# Lumiboard-SMD-DX-v003-stew.net
KiCad netlist of a schematic drawn in EAGLE
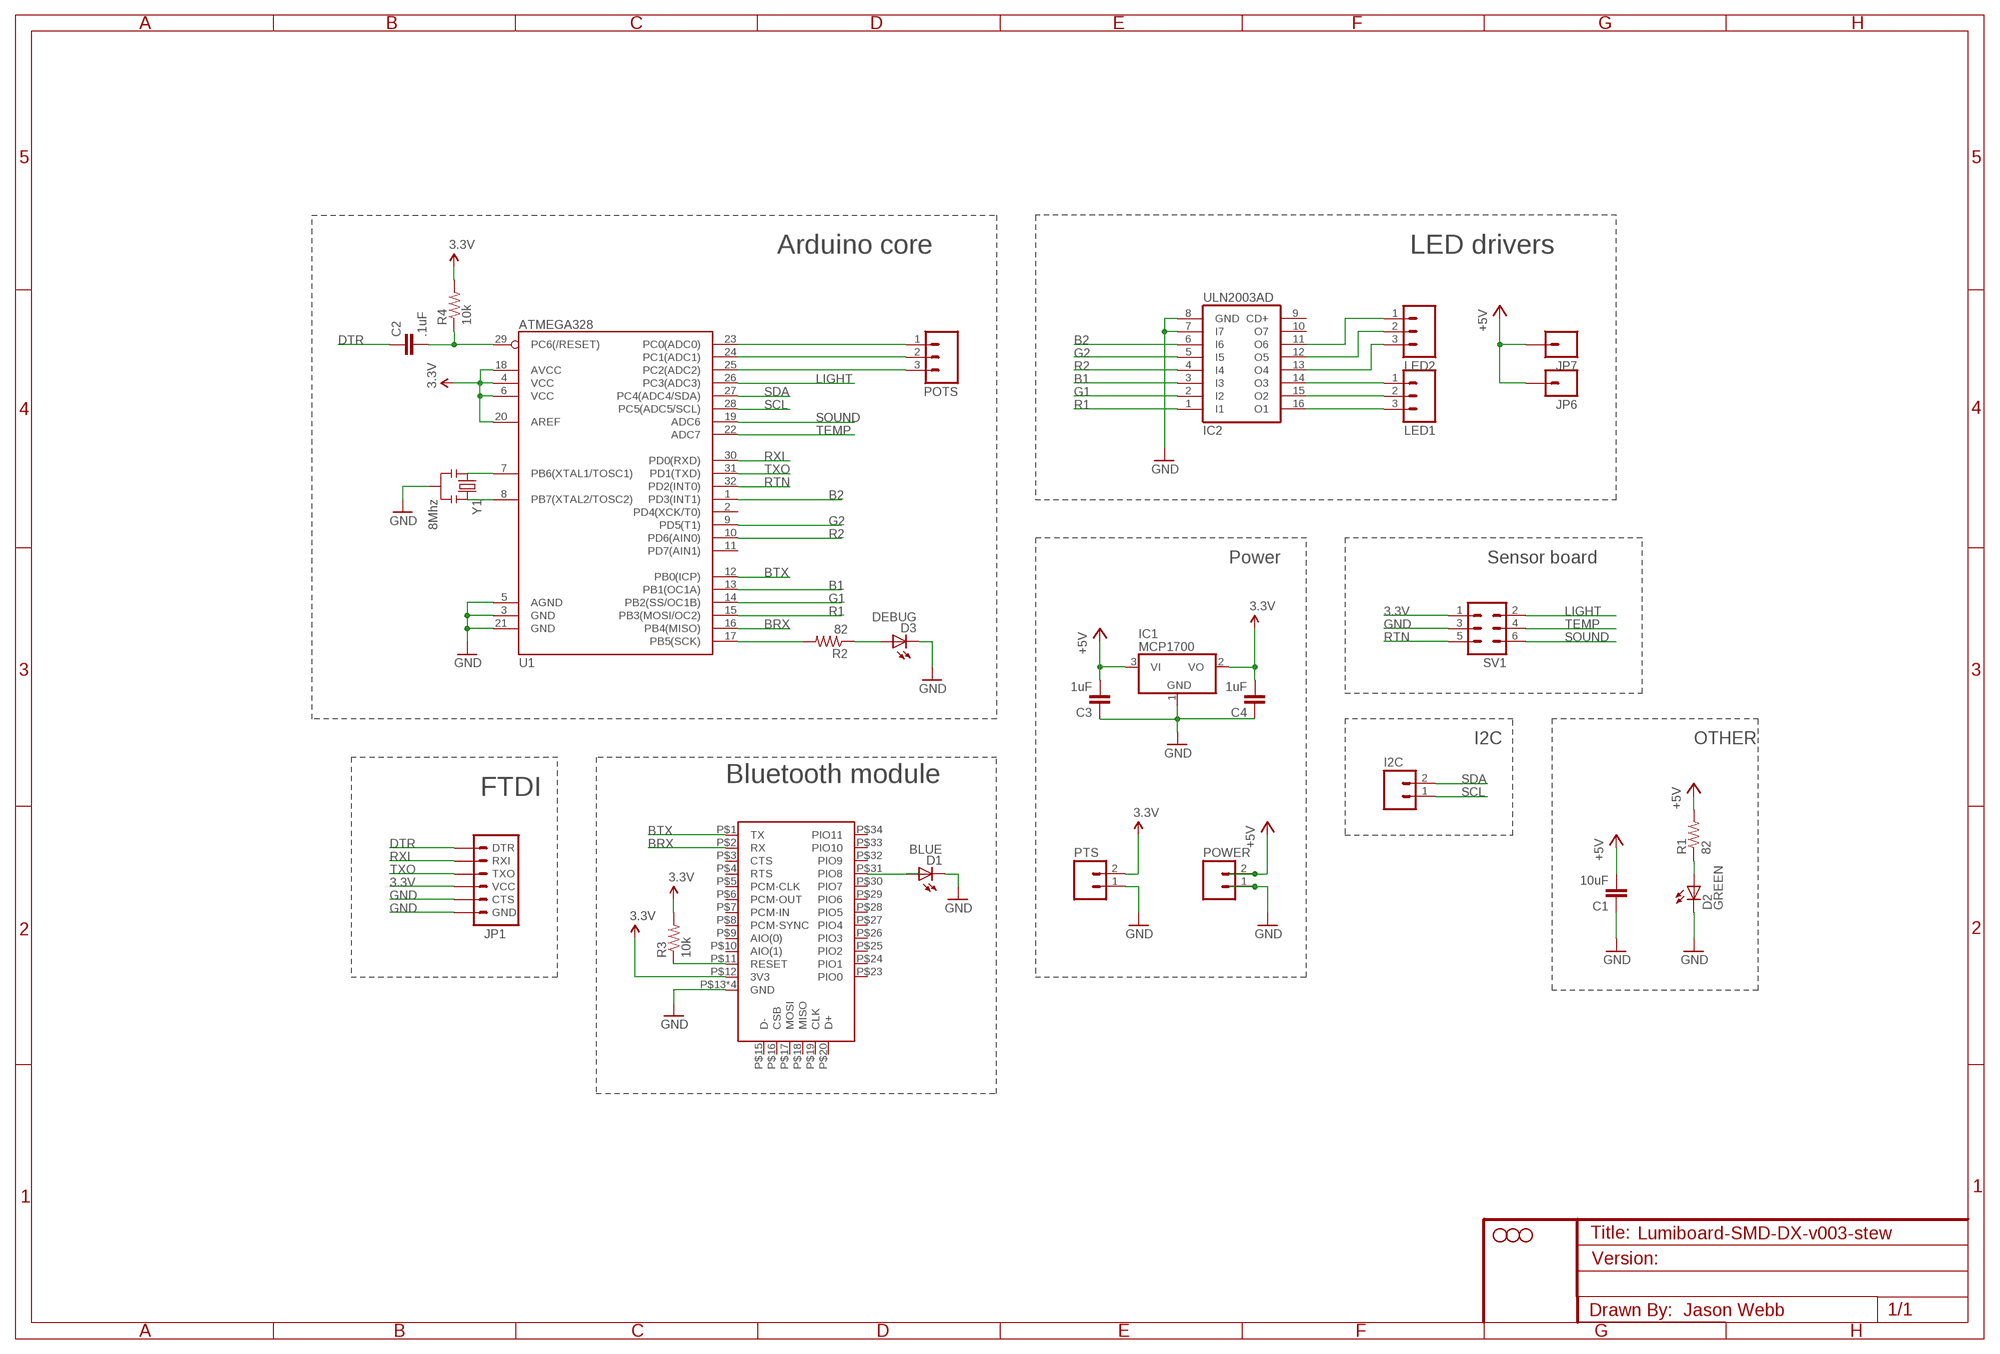
[diagram p0: schematic, sheet 1]

(export (version "E")
  (design (tool "Eeschema 10.0.6"))
  (components
    (comp (ref "C1")
      (value "10uF")
      (footprint "eagle-import:0805")
      (libsource (lib "eagle-import") (part "CAP0805"))
    )
    (comp (ref "C2")
      (value ".1uF")
      (footprint "eagle-import:0805")
      (libsource (lib "eagle-import") (part "CAP0805"))
    )
    (comp (ref "C3")
      (value "1uF")
      (footprint "eagle-import:0805")
      (libsource (lib "eagle-import") (part "CAP0805"))
    )
    (comp (ref "C4")
      (value "1uF")
      (footprint "eagle-import:0805")
      (libsource (lib "eagle-import") (part "CAP0805"))
    )
    (comp (ref "D1")
      (value "BLUE")
      (footprint "eagle-import:CHIPLED_0805")
      (libsource (lib "eagle-import") (part "LEDCHIPLED_0805"))
    )
    (comp (ref "D2")
      (value "GREEN")
      (footprint "eagle-import:CHIPLED_0805")
      (libsource (lib "eagle-import") (part "LEDCHIPLED_0805"))
    )
    (comp (ref "D3")
      (value "DEBUG")
      (footprint "eagle-import:CHIPLED_0805")
      (libsource (lib "eagle-import") (part "LEDCHIPLED_0805"))
    )
    (comp (ref "I2C")
      (value "M02PTH")
      (footprint "eagle-import:1X02")
      (libsource (lib "eagle-import") (part "M02PTH"))
    )
    (comp (ref "IC1")
      (value "MCP1700")
      (footprint "eagle-import:SOT23")
      (libsource (lib "eagle-import") (part "MCP1703CB"))
    )
    (comp (ref "IC2")
      (value "ULN2003AD")
      (footprint "eagle-import:SO16")
      (libsource (lib "eagle-import") (part "ULN2003AD"))
    )
    (comp (ref "JP1")
      (value "ARDUINO_SERIAL_PROGRAMLOCK")
      (footprint "eagle-import:1X06_LOCK")
      (libsource (lib "eagle-import") (part "ARDUINO_SERIAL_PROGRAMLOCK"))
    )
    (comp (ref "JP2")
      (value "STAND-OFFTIGHT")
      (footprint "eagle-import:STAND-OFF-TIGHT")
      (libsource (lib "eagle-import") (part "STAND-OFFTIGHT"))
    )
    (comp (ref "JP4")
      (value "STAND-OFFTIGHT")
      (footprint "eagle-import:STAND-OFF-TIGHT")
      (libsource (lib "eagle-import") (part "STAND-OFFTIGHT"))
    )
    (comp (ref "JP5")
      (value "STAND-OFFTIGHT")
      (footprint "eagle-import:STAND-OFF-TIGHT")
      (libsource (lib "eagle-import") (part "STAND-OFFTIGHT"))
    )
    (comp (ref "JP6")
      (value "M01PTH")
      (footprint "eagle-import:1X01")
      (libsource (lib "eagle-import") (part "M01PTH"))
    )
    (comp (ref "JP7")
      (value "M01PTH")
      (footprint "eagle-import:1X01")
      (libsource (lib "eagle-import") (part "M01PTH"))
    )
    (comp (ref "LED1")
      (value "M03PTH")
      (footprint "eagle-import:1X03")
      (libsource (lib "eagle-import") (part "M03PTH"))
    )
    (comp (ref "LED2")
      (value "M03PTH")
      (footprint "eagle-import:1X03")
      (libsource (lib "eagle-import") (part "M03PTH"))
    )
    (comp (ref "POTS")
      (value "M03PTH")
      (footprint "eagle-import:1X03")
      (libsource (lib "eagle-import") (part "M03PTH"))
    )
    (comp (ref "POWER")
      (value "M02PTH")
      (footprint "eagle-import:1X02")
      (libsource (lib "eagle-import") (part "M02PTH"))
    )
    (comp (ref "PTS")
      (value "M02PTH")
      (footprint "eagle-import:1X02")
      (libsource (lib "eagle-import") (part "M02PTH"))
    )
    (comp (ref "R1")
      (value "82")
      (footprint "eagle-import:R0805")
      (libsource (lib "eagle-import") (part "R-US_R0805"))
    )
    (comp (ref "R2")
      (value "82")
      (footprint "eagle-import:R0805")
      (libsource (lib "eagle-import") (part "R-US_R0805"))
    )
    (comp (ref "R3")
      (value "10k")
      (footprint "eagle-import:R0805")
      (libsource (lib "eagle-import") (part "R-US_R0805"))
    )
    (comp (ref "R4")
      (value "10k")
      (footprint "eagle-import:R0805")
      (libsource (lib "eagle-import") (part "R-US_R0805"))
    )
    (comp (ref "SV1")
      (value "ML6")
      (footprint "eagle-import:ML6")
      (libsource (lib "eagle-import") (part "ML6"))
    )
    (comp (ref "U1")
      (value "ATMEGA328")
      (footprint "eagle-import:TQFP32-08")
      (libsource (lib "eagle-import") (part "ATMEGA168"))
    )
    (comp (ref "U2")
      (value "DX_BT_MODULE")
      (footprint "eagle-import:DXBLUETOOTHMODULE")
      (libsource (lib "eagle-import") (part "DX_BT_MODULE"))
    )
    (comp (ref "Y1")
      (value "8Mhz")
      (footprint "eagle-import:RESONATOR-SMD")
      (libsource (lib "eagle-import") (part "RESONATORSMD"))
    )
  )
  (nets
    (net (code "1") (name "+5V") (class "Default")
      (node (ref "C1") (pin "2") (pinfunction "2_2") (pintype "passive"))
      (node (ref "C3") (pin "2") (pinfunction "2_2") (pintype "passive"))
      (node (ref "IC1") (pin "3") (pinfunction "VI_3") (pintype "input"))
      (node (ref "JP6") (pin "1") (pinfunction "1_1") (pintype "passive"))
      (node (ref "JP7") (pin "1") (pinfunction "1_1") (pintype "passive"))
      (node (ref "POWER") (pin "2") (pinfunction "2_2") (pintype "passive"))
      (node (ref "R1") (pin "2") (pinfunction "2_2") (pintype "passive"))
    )
    (net (code "2") (name "/B1") (class "Default")
      (node (ref "IC2") (pin "3") (pinfunction "I3_3") (pintype "input"))
      (node (ref "U1") (pin "13") (pinfunction "PB1(OC1A)_13") (pintype "bidirectional"))
    )
    (net (code "3") (name "/B2") (class "Default")
      (node (ref "IC2") (pin "6") (pinfunction "I6_6") (pintype "input"))
      (node (ref "U1") (pin "1") (pinfunction "PD3(INT1)_1") (pintype "bidirectional"))
    )
    (net (code "4") (name "/BRX") (class "Default")
      (node (ref "U1") (pin "16") (pinfunction "PB4(MISO)_16") (pintype "bidirectional"))
      (node (ref "U2") (pin "P$2") (pinfunction "RX_P$2") (pintype "input"))
    )
    (net (code "5") (name "/BTX") (class "Default")
      (node (ref "U1") (pin "12") (pinfunction "PB0(ICP)_12") (pintype "bidirectional"))
      (node (ref "U2") (pin "P$1") (pinfunction "TX_P$1") (pintype "output"))
    )
    (net (code "6") (name "/DTR") (class "Default")
      (node (ref "C2") (pin "1") (pinfunction "1_1") (pintype "passive"))
      (node (ref "JP1") (pin "1") (pinfunction "DTR_1") (pintype "passive"))
    )
    (net (code "7") (name "/G1") (class "Default")
      (node (ref "IC2") (pin "2") (pinfunction "I2_2") (pintype "input"))
      (node (ref "U1") (pin "14") (pinfunction "PB2(SS/OC1B)_14") (pintype "bidirectional"))
    )
    (net (code "8") (name "/G2") (class "Default")
      (node (ref "IC2") (pin "5") (pinfunction "I5_5") (pintype "input"))
      (node (ref "U1") (pin "9") (pinfunction "PD5(T1)_9") (pintype "bidirectional"))
    )
    (net (code "9") (name "/LIGHT") (class "Default")
      (node (ref "SV1") (pin "2") (pinfunction "2_2") (pintype "passive"))
      (node (ref "U1") (pin "26") (pinfunction "PC3(ADC3)_26") (pintype "bidirectional"))
    )
    (net (code "10") (name "/R1") (class "Default")
      (node (ref "IC2") (pin "1") (pinfunction "I1_1") (pintype "input"))
      (node (ref "U1") (pin "15") (pinfunction "PB3(MOSI/OC2)_15") (pintype "bidirectional"))
    )
    (net (code "11") (name "/R2") (class "Default")
      (node (ref "IC2") (pin "4") (pinfunction "I4_4") (pintype "input"))
      (node (ref "U1") (pin "10") (pinfunction "PD6(AIN0)_10") (pintype "bidirectional"))
    )
    (net (code "12") (name "/RTN") (class "Default")
      (node (ref "SV1") (pin "5") (pinfunction "5_5") (pintype "passive"))
      (node (ref "U1") (pin "32") (pinfunction "PD2(INT0)_32") (pintype "bidirectional"))
    )
    (net (code "13") (name "/RXI") (class "Default")
      (node (ref "JP1") (pin "2") (pinfunction "RXI_2") (pintype "passive"))
      (node (ref "U1") (pin "30") (pinfunction "PD0(RXD)_30") (pintype "bidirectional"))
    )
    (net (code "14") (name "/SCL") (class "Default")
      (node (ref "I2C") (pin "1") (pinfunction "1_1") (pintype "passive"))
      (node (ref "U1") (pin "28") (pinfunction "PC5(ADC5/SCL)_28") (pintype "bidirectional"))
    )
    (net (code "15") (name "/SDA") (class "Default")
      (node (ref "I2C") (pin "2") (pinfunction "2_2") (pintype "passive"))
      (node (ref "U1") (pin "27") (pinfunction "PC4(ADC4/SDA)_27") (pintype "bidirectional"))
    )
    (net (code "16") (name "/SOUND") (class "Default")
      (node (ref "SV1") (pin "6") (pinfunction "6_6") (pintype "passive"))
      (node (ref "U1") (pin "19") (pinfunction "ADC6_19") (pintype "bidirectional"))
    )
    (net (code "17") (name "/TEMP") (class "Default")
      (node (ref "SV1") (pin "4") (pinfunction "4_4") (pintype "passive"))
      (node (ref "U1") (pin "22") (pinfunction "ADC7_22") (pintype "bidirectional"))
    )
    (net (code "18") (name "/TXO") (class "Default")
      (node (ref "JP1") (pin "3") (pinfunction "TXO_3") (pintype "passive"))
      (node (ref "U1") (pin "31") (pinfunction "PD1(TXD)_31") (pintype "bidirectional"))
    )
    (net (code "19") (name "3.3V") (class "Default")
      (node (ref "C4") (pin "2") (pinfunction "2_2") (pintype "passive"))
      (node (ref "IC1") (pin "2") (pinfunction "VO_2") (pintype "passive"))
      (node (ref "JP1") (pin "4") (pinfunction "VCC_4") (pintype "passive"))
      (node (ref "PTS") (pin "2") (pinfunction "2_2") (pintype "passive"))
      (node (ref "R3") (pin "2") (pinfunction "2_2") (pintype "passive"))
      (node (ref "R4") (pin "2") (pinfunction "2_2") (pintype "passive"))
      (node (ref "SV1") (pin "1") (pinfunction "1_1") (pintype "passive"))
      (node (ref "U1") (pin "18") (pinfunction "AVCC_18") (pintype "bidirectional"))
      (node (ref "U1") (pin "20") (pinfunction "AREF_20") (pintype "bidirectional"))
      (node (ref "U1") (pin "4") (pinfunction "VCC_4") (pintype "bidirectional"))
      (node (ref "U1") (pin "6") (pinfunction "VCC_6") (pintype "bidirectional"))
      (node (ref "U2") (pin "P$12") (pinfunction "3V3_P$12") (pintype "power_in"))
    )
    (net (code "20") (name "GND") (class "Default")
      (node (ref "C1") (pin "1") (pinfunction "1_1") (pintype "passive"))
      (node (ref "C3") (pin "1") (pinfunction "1_1") (pintype "passive"))
      (node (ref "C4") (pin "1") (pinfunction "1_1") (pintype "passive"))
      (node (ref "D1") (pin "C") (pinfunction "C_C") (pintype "passive"))
      (node (ref "D2") (pin "C") (pinfunction "C_C") (pintype "passive"))
      (node (ref "D3") (pin "C") (pinfunction "C_C") (pintype "passive"))
      (node (ref "IC1") (pin "1") (pinfunction "GND_1") (pintype "passive"))
      (node (ref "IC2") (pin "7") (pinfunction "I7_7") (pintype "input"))
      (node (ref "IC2") (pin "8") (pinfunction "GND_8") (pintype "power_in"))
      (node (ref "JP1") (pin "5") (pinfunction "CTS_5") (pintype "passive"))
      (node (ref "JP1") (pin "6") (pinfunction "GND_6") (pintype "passive"))
      (node (ref "POWER") (pin "1") (pinfunction "1_1") (pintype "passive"))
      (node (ref "PTS") (pin "1") (pinfunction "1_1") (pintype "passive"))
      (node (ref "SV1") (pin "3") (pinfunction "3_3") (pintype "passive"))
      (node (ref "U1") (pin "21") (pinfunction "GND_21") (pintype "bidirectional"))
      (node (ref "U1") (pin "3") (pinfunction "GND_3") (pintype "bidirectional"))
      (node (ref "U1") (pin "5") (pinfunction "AGND_5") (pintype "bidirectional"))
      (node (ref "U2") (pin "P$13") (pinfunction "GND_P$13") (pintype "power_in"))
      (node (ref "U2") (pin "P$14") (pinfunction "GND_P$14") (pintype "power_in"))
      (node (ref "U2") (pin "P$21") (pinfunction "GND_P$21") (pintype "power_in"))
      (node (ref "U2") (pin "P$22") (pinfunction "GND_P$22") (pintype "power_in"))
      (node (ref "Y1") (pin "2") (pinfunction "2_2") (pintype "passive"))
    )
    (net (code "21") (name "Net-(D2-PadA)") (class "Default")
      (node (ref "D2") (pin "A") (pinfunction "A_A") (pintype "passive"))
      (node (ref "R1") (pin "1") (pinfunction "1_1") (pintype "passive"))
    )
    (net (code "22") (name "Net-(D3-PadA)") (class "Default")
      (node (ref "D3") (pin "A") (pinfunction "A_A") (pintype "passive"))
      (node (ref "R2") (pin "1") (pinfunction "1_1") (pintype "passive"))
    )
    (net (code "23") (name "Net-(IC2-O1)") (class "Default")
      (node (ref "IC2") (pin "16") (pinfunction "O1_16") (pintype "open_collector"))
      (node (ref "LED1") (pin "3") (pinfunction "3_3") (pintype "passive"))
    )
    (net (code "24") (name "Net-(IC2-O2)") (class "Default")
      (node (ref "IC2") (pin "15") (pinfunction "O2_15") (pintype "open_collector"))
      (node (ref "LED1") (pin "2") (pinfunction "2_2") (pintype "passive"))
    )
    (net (code "25") (name "Net-(IC2-O3)") (class "Default")
      (node (ref "IC2") (pin "14") (pinfunction "O3_14") (pintype "open_collector"))
      (node (ref "LED1") (pin "1") (pinfunction "1_1") (pintype "passive"))
    )
    (net (code "26") (name "Net-(IC2-O4)") (class "Default")
      (node (ref "IC2") (pin "13") (pinfunction "O4_13") (pintype "open_collector"))
      (node (ref "LED2") (pin "3") (pinfunction "3_3") (pintype "passive"))
    )
    (net (code "27") (name "Net-(IC2-O5)") (class "Default")
      (node (ref "IC2") (pin "12") (pinfunction "O5_12") (pintype "open_collector"))
      (node (ref "LED2") (pin "2") (pinfunction "2_2") (pintype "passive"))
    )
    (net (code "28") (name "Net-(IC2-O6)") (class "Default")
      (node (ref "IC2") (pin "11") (pinfunction "O6_11") (pintype "open_collector"))
      (node (ref "LED2") (pin "1") (pinfunction "1_1") (pintype "passive"))
    )
    (net (code "29") (name "Net-(U1-PB5(SCK))") (class "Default")
      (node (ref "R2") (pin "2") (pinfunction "2_2") (pintype "passive"))
      (node (ref "U1") (pin "17") (pinfunction "PB5(SCK)_17") (pintype "bidirectional"))
    )
    (net (code "30") (name "Net-(U1-PB6(XTAL1{slash}TOSC1))") (class "Default")
      (node (ref "U1") (pin "7") (pinfunction "PB6(XTAL1/TOSC1)_7") (pintype "bidirectional"))
      (node (ref "Y1") (pin "1") (pinfunction "1_1") (pintype "passive"))
    )
    (net (code "31") (name "Net-(U1-PB7(XTAL2{slash}TOSC2))") (class "Default")
      (node (ref "U1") (pin "8") (pinfunction "PB7(XTAL2/TOSC2)_8") (pintype "bidirectional"))
      (node (ref "Y1") (pin "3") (pinfunction "3_3") (pintype "passive"))
    )
    (net (code "32") (name "Net-(U1-PC0(ADC0))") (class "Default")
      (node (ref "POTS") (pin "1") (pinfunction "1_1") (pintype "passive"))
      (node (ref "U1") (pin "23") (pinfunction "PC0(ADC0)_23") (pintype "bidirectional"))
    )
    (net (code "33") (name "Net-(U1-PC1(ADC1))") (class "Default")
      (node (ref "POTS") (pin "2") (pinfunction "2_2") (pintype "passive"))
      (node (ref "U1") (pin "24") (pinfunction "PC1(ADC1)_24") (pintype "bidirectional"))
    )
    (net (code "34") (name "Net-(U1-PC2(ADC2))") (class "Default")
      (node (ref "POTS") (pin "3") (pinfunction "3_3") (pintype "passive"))
      (node (ref "U1") (pin "25") (pinfunction "PC2(ADC2)_25") (pintype "bidirectional"))
    )
    (net (code "35") (name "Net-(U1-PC6({slash}RESET))") (class "Default")
      (node (ref "C2") (pin "2") (pinfunction "2_2") (pintype "passive"))
      (node (ref "R4") (pin "1") (pinfunction "1_1") (pintype "passive"))
      (node (ref "U1") (pin "29") (pinfunction "PC6(/RESET)_29") (pintype "bidirectional"))
    )
    (net (code "36") (name "Net-(U2-PIO8)") (class "Default")
      (node (ref "D1") (pin "A") (pinfunction "A_A") (pintype "passive"))
      (node (ref "U2") (pin "P$31") (pinfunction "PIO8_P$31") (pintype "bidirectional"))
    )
    (net (code "37") (name "Net-(U2-RESET)") (class "Default")
      (node (ref "R3") (pin "1") (pinfunction "1_1") (pintype "passive"))
      (node (ref "U2") (pin "P$11") (pinfunction "RESET_P$11") (pintype "input"))
    )
    (net (code "38") (name "unconnected-(IC2-CD+-Pad9)") (class "Default")
      (node (ref "IC2") (pin "9") (pinfunction "CD+_9") (pintype "passive"))
    )
    (net (code "39") (name "unconnected-(IC2-O7-Pad10)") (class "Default")
      (node (ref "IC2") (pin "10") (pinfunction "O7_10") (pintype "open_collector"))
    )
    (net (code "40") (name "unconnected-(U1-PD4(XCK{slash}T0)-Pad2)") (class "Default")
      (node (ref "U1") (pin "2") (pinfunction "PD4(XCK/T0)_2") (pintype "bidirectional"))
    )
    (net (code "41") (name "unconnected-(U1-PD7(AIN1)-Pad11)") (class "Default")
      (node (ref "U1") (pin "11") (pinfunction "PD7(AIN1)_11") (pintype "bidirectional"))
    )
    (net (code "42") (name "unconnected-(U2-AIO(0)-PadP$9)") (class "Default")
      (node (ref "U2") (pin "P$9") (pinfunction "AIO(0)_P$9") (pintype "bidirectional"))
    )
    (net (code "43") (name "unconnected-(U2-AIO(1)-PadP$10)") (class "Default")
      (node (ref "U2") (pin "P$10") (pinfunction "AIO(1)_P$10") (pintype "bidirectional"))
    )
    (net (code "44") (name "unconnected-(U2-CLK-PadP$19)") (class "Default")
      (node (ref "U2") (pin "P$19") (pinfunction "CLK_P$19") (pintype "input"))
    )
    (net (code "45") (name "unconnected-(U2-CSB-PadP$16)") (class "Default")
      (node (ref "U2") (pin "P$16") (pinfunction "CSB_P$16") (pintype "input"))
    )
    (net (code "46") (name "unconnected-(U2-CTS-PadP$3)") (class "Default")
      (node (ref "U2") (pin "P$3") (pinfunction "CTS_P$3") (pintype "input"))
    )
    (net (code "47") (name "unconnected-(U2-D+-PadP$20)") (class "Default")
      (node (ref "U2") (pin "P$20") (pinfunction "D+_P$20") (pintype "bidirectional"))
    )
    (net (code "48") (name "unconnected-(U2-D--PadP$15)") (class "Default")
      (node (ref "U2") (pin "P$15") (pinfunction "D-_P$15") (pintype "bidirectional"))
    )
    (net (code "49") (name "unconnected-(U2-MISO-PadP$18)") (class "Default")
      (node (ref "U2") (pin "P$18") (pinfunction "MISO_P$18") (pintype "output"))
    )
    (net (code "50") (name "unconnected-(U2-MOSI-PadP$17)") (class "Default")
      (node (ref "U2") (pin "P$17") (pinfunction "MOSI_P$17") (pintype "input"))
    )
    (net (code "51") (name "unconnected-(U2-PCM-CLK-PadP$5)") (class "Default")
      (node (ref "U2") (pin "P$5") (pinfunction "PCM-CLK_P$5") (pintype "bidirectional"))
    )
    (net (code "52") (name "unconnected-(U2-PCM-IN-PadP$7)") (class "Default")
      (node (ref "U2") (pin "P$7") (pinfunction "PCM-IN_P$7") (pintype "input"))
    )
    (net (code "53") (name "unconnected-(U2-PCM-OUT-PadP$6)") (class "Default")
      (node (ref "U2") (pin "P$6") (pinfunction "PCM-OUT_P$6") (pintype "output"))
    )
    (net (code "54") (name "unconnected-(U2-PCM-SYNC-PadP$8)") (class "Default")
      (node (ref "U2") (pin "P$8") (pinfunction "PCM-SYNC_P$8") (pintype "bidirectional"))
    )
    (net (code "55") (name "unconnected-(U2-PIO0-PadP$23)") (class "Default")
      (node (ref "U2") (pin "P$23") (pinfunction "PIO0_P$23") (pintype "bidirectional"))
    )
    (net (code "56") (name "unconnected-(U2-PIO1-PadP$24)") (class "Default")
      (node (ref "U2") (pin "P$24") (pinfunction "PIO1_P$24") (pintype "bidirectional"))
    )
    (net (code "57") (name "unconnected-(U2-PIO2-PadP$25)") (class "Default")
      (node (ref "U2") (pin "P$25") (pinfunction "PIO2_P$25") (pintype "bidirectional"))
    )
    (net (code "58") (name "unconnected-(U2-PIO3-PadP$26)") (class "Default")
      (node (ref "U2") (pin "P$26") (pinfunction "PIO3_P$26") (pintype "bidirectional"))
    )
    (net (code "59") (name "unconnected-(U2-PIO4-PadP$27)") (class "Default")
      (node (ref "U2") (pin "P$27") (pinfunction "PIO4_P$27") (pintype "bidirectional"))
    )
    (net (code "60") (name "unconnected-(U2-PIO5-PadP$28)") (class "Default")
      (node (ref "U2") (pin "P$28") (pinfunction "PIO5_P$28") (pintype "bidirectional"))
    )
    (net (code "61") (name "unconnected-(U2-PIO6-PadP$29)") (class "Default")
      (node (ref "U2") (pin "P$29") (pinfunction "PIO6_P$29") (pintype "bidirectional"))
    )
    (net (code "62") (name "unconnected-(U2-PIO7-PadP$30)") (class "Default")
      (node (ref "U2") (pin "P$30") (pinfunction "PIO7_P$30") (pintype "bidirectional"))
    )
    (net (code "63") (name "unconnected-(U2-PIO9-PadP$32)") (class "Default")
      (node (ref "U2") (pin "P$32") (pinfunction "PIO9_P$32") (pintype "bidirectional"))
    )
    (net (code "64") (name "unconnected-(U2-PIO10-PadP$33)") (class "Default")
      (node (ref "U2") (pin "P$33") (pinfunction "PIO10_P$33") (pintype "bidirectional"))
    )
    (net (code "65") (name "unconnected-(U2-PIO11-PadP$34)") (class "Default")
      (node (ref "U2") (pin "P$34") (pinfunction "PIO11_P$34") (pintype "bidirectional"))
    )
    (net (code "66") (name "unconnected-(U2-RTS-PadP$4)") (class "Default")
      (node (ref "U2") (pin "P$4") (pinfunction "RTS_P$4") (pintype "output"))
    )
  )
)
